# SENSOR_BOARD_2_1_layer.net
KiCad netlist of a schematic drawn in EAGLE
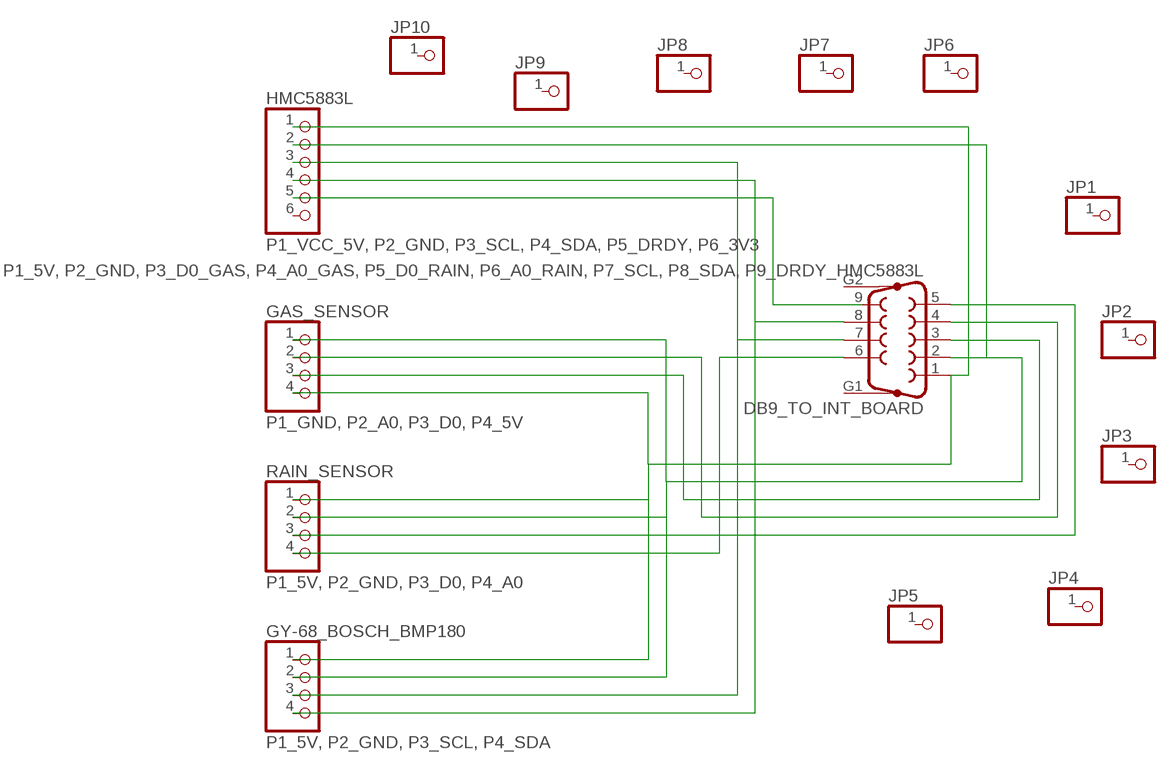
[diagram p0: schematic, sheet 1]

(export (version "E")
  (design (tool "Eeschema 10.0.6"))
  (components
    (comp (ref "DB9_TO_INT_BOARD")
      (value "P1_5V, P2_GND, P3_D0_GAS, P4_A0_GAS, P5_D0_RAIN, P6_A0_RAIN, P7_SCL, P8_SDA, P9_DRDY_HMC5883L")
      (footprint "eagle-import:F09HP")
      (libsource (lib "eagle-import") (part "F09HP"))
    )
    (comp (ref "GAS_SENSOR")
      (value "P1_GND, P2_A0, P3_D0, P4_5V")
      (footprint "eagle-import:1X04")
      (libsource (lib "eagle-import") (part "PINHD-1X4"))
    )
    (comp (ref "GY-68_BOSCH_BMP180")
      (value "P1_5V, P2_GND, P3_SCL, P4_SDA")
      (footprint "eagle-import:1X04")
      (libsource (lib "eagle-import") (part "PINHD-1X4"))
    )
    (comp (ref "HMC5883L")
      (value "P1_VCC_5V, P2_GND, P3_SCL, P4_SDA, P5_DRDY, P6_3V3")
      (footprint "eagle-import:1X06")
      (libsource (lib "eagle-import") (part "PINHD-1X6"))
    )
    (comp (ref "JP1")
      (value "PINHD-1X1")
      (footprint "eagle-import:1X01")
      (libsource (lib "eagle-import") (part "PINHD-1X1"))
    )
    (comp (ref "JP2")
      (value "PINHD-1X1")
      (footprint "eagle-import:1X01")
      (libsource (lib "eagle-import") (part "PINHD-1X1"))
    )
    (comp (ref "JP3")
      (value "PINHD-1X1")
      (footprint "eagle-import:1X01")
      (libsource (lib "eagle-import") (part "PINHD-1X1"))
    )
    (comp (ref "JP4")
      (value "PINHD-1X1")
      (footprint "eagle-import:1X01")
      (libsource (lib "eagle-import") (part "PINHD-1X1"))
    )
    (comp (ref "JP5")
      (value "PINHD-1X1")
      (footprint "eagle-import:1X01")
      (libsource (lib "eagle-import") (part "PINHD-1X1"))
    )
    (comp (ref "JP6")
      (value "PINHD-1X1")
      (footprint "eagle-import:1X01")
      (libsource (lib "eagle-import") (part "PINHD-1X1"))
    )
    (comp (ref "JP7")
      (value "PINHD-1X1")
      (footprint "eagle-import:1X01")
      (libsource (lib "eagle-import") (part "PINHD-1X1"))
    )
    (comp (ref "JP8")
      (value "PINHD-1X1")
      (footprint "eagle-import:1X01")
      (libsource (lib "eagle-import") (part "PINHD-1X1"))
    )
    (comp (ref "JP9")
      (value "PINHD-1X1")
      (footprint "eagle-import:1X01")
      (libsource (lib "eagle-import") (part "PINHD-1X1"))
    )
    (comp (ref "JP10")
      (value "PINHD-1X1")
      (footprint "eagle-import:1X01")
      (libsource (lib "eagle-import") (part "PINHD-1X1"))
    )
    (comp (ref "RAIN_SENSOR")
      (value "P1_5V, P2_GND, P3_D0, P4_A0")
      (footprint "eagle-import:1X04")
      (libsource (lib "eagle-import") (part "PINHD-1X4"))
    )
  )
  (nets
    (net (code "1") (name "Net-(DB9_TO_INT_BOARD-Pad1)") (class "Default")
      (node (ref "DB9_TO_INT_BOARD") (pin "1") (pinfunction "1_1") (pintype "passive"))
      (node (ref "GAS_SENSOR") (pin "4") (pinfunction "4_4") (pintype "passive"))
      (node (ref "GY-68_BOSCH_BMP180") (pin "1") (pinfunction "1_1") (pintype "passive"))
      (node (ref "HMC5883L") (pin "1") (pinfunction "1_1") (pintype "passive"))
      (node (ref "RAIN_SENSOR") (pin "1") (pinfunction "1_1") (pintype "passive"))
    )
    (net (code "2") (name "Net-(DB9_TO_INT_BOARD-Pad2)") (class "Default")
      (node (ref "DB9_TO_INT_BOARD") (pin "2") (pinfunction "2_2") (pintype "passive"))
      (node (ref "GAS_SENSOR") (pin "1") (pinfunction "1_1") (pintype "passive"))
      (node (ref "GY-68_BOSCH_BMP180") (pin "2") (pinfunction "2_2") (pintype "passive"))
      (node (ref "HMC5883L") (pin "2") (pinfunction "2_2") (pintype "passive"))
      (node (ref "RAIN_SENSOR") (pin "2") (pinfunction "2_2") (pintype "passive"))
    )
    (net (code "3") (name "Net-(DB9_TO_INT_BOARD-Pad3)") (class "Default")
      (node (ref "DB9_TO_INT_BOARD") (pin "3") (pinfunction "3_3") (pintype "passive"))
      (node (ref "GAS_SENSOR") (pin "3") (pinfunction "3_3") (pintype "passive"))
    )
    (net (code "4") (name "Net-(DB9_TO_INT_BOARD-Pad4)") (class "Default")
      (node (ref "DB9_TO_INT_BOARD") (pin "4") (pinfunction "4_4") (pintype "passive"))
      (node (ref "GAS_SENSOR") (pin "2") (pinfunction "2_2") (pintype "passive"))
    )
    (net (code "5") (name "Net-(DB9_TO_INT_BOARD-Pad5)") (class "Default")
      (node (ref "DB9_TO_INT_BOARD") (pin "5") (pinfunction "5_5") (pintype "passive"))
      (node (ref "RAIN_SENSOR") (pin "3") (pinfunction "3_3") (pintype "passive"))
    )
    (net (code "6") (name "Net-(DB9_TO_INT_BOARD-Pad6)") (class "Default")
      (node (ref "DB9_TO_INT_BOARD") (pin "6") (pinfunction "6_6") (pintype "passive"))
      (node (ref "RAIN_SENSOR") (pin "4") (pinfunction "4_4") (pintype "passive"))
    )
    (net (code "7") (name "Net-(DB9_TO_INT_BOARD-Pad7)") (class "Default")
      (node (ref "DB9_TO_INT_BOARD") (pin "7") (pinfunction "7_7") (pintype "passive"))
      (node (ref "GY-68_BOSCH_BMP180") (pin "3") (pinfunction "3_3") (pintype "passive"))
      (node (ref "HMC5883L") (pin "3") (pinfunction "3_3") (pintype "passive"))
    )
    (net (code "8") (name "Net-(DB9_TO_INT_BOARD-Pad8)") (class "Default")
      (node (ref "DB9_TO_INT_BOARD") (pin "8") (pinfunction "8_8") (pintype "passive"))
      (node (ref "GY-68_BOSCH_BMP180") (pin "4") (pinfunction "4_4") (pintype "passive"))
      (node (ref "HMC5883L") (pin "4") (pinfunction "4_4") (pintype "passive"))
    )
    (net (code "9") (name "unconnected-(DB9_TO_INT_BOARD-Pad9)") (class "Default")
      (node (ref "DB9_TO_INT_BOARD") (pin "9") (pinfunction "9_9") (pintype "passive"))
    )
    (net (code "10") (name "unconnected-(DB9_TO_INT_BOARD-PadG1)") (class "Default")
      (node (ref "DB9_TO_INT_BOARD") (pin "G1") (pinfunction "G1_G1") (pintype "passive"))
    )
    (net (code "11") (name "unconnected-(DB9_TO_INT_BOARD-PadG2)") (class "Default")
      (node (ref "DB9_TO_INT_BOARD") (pin "G2") (pinfunction "G2_G2") (pintype "passive"))
    )
    (net (code "12") (name "unconnected-(HMC5883L-Pad5)") (class "Default")
      (node (ref "HMC5883L") (pin "5") (pinfunction "5_5") (pintype "passive"))
    )
    (net (code "13") (name "unconnected-(HMC5883L-Pad6)") (class "Default")
      (node (ref "HMC5883L") (pin "6") (pinfunction "6_6") (pintype "passive"))
    )
    (net (code "14") (name "unconnected-(JP1-Pad1)") (class "Default")
      (node (ref "JP1") (pin "1") (pinfunction "1_1") (pintype "passive"))
    )
    (net (code "15") (name "unconnected-(JP2-Pad1)") (class "Default")
      (node (ref "JP2") (pin "1") (pinfunction "1_1") (pintype "passive"))
    )
    (net (code "16") (name "unconnected-(JP3-Pad1)") (class "Default")
      (node (ref "JP3") (pin "1") (pinfunction "1_1") (pintype "passive"))
    )
    (net (code "17") (name "unconnected-(JP4-Pad1)") (class "Default")
      (node (ref "JP4") (pin "1") (pinfunction "1_1") (pintype "passive"))
    )
    (net (code "18") (name "unconnected-(JP5-Pad1)") (class "Default")
      (node (ref "JP5") (pin "1") (pinfunction "1_1") (pintype "passive"))
    )
    (net (code "19") (name "unconnected-(JP6-Pad1)") (class "Default")
      (node (ref "JP6") (pin "1") (pinfunction "1_1") (pintype "passive"))
    )
    (net (code "20") (name "unconnected-(JP7-Pad1)") (class "Default")
      (node (ref "JP7") (pin "1") (pinfunction "1_1") (pintype "passive"))
    )
    (net (code "21") (name "unconnected-(JP8-Pad1)") (class "Default")
      (node (ref "JP8") (pin "1") (pinfunction "1_1") (pintype "passive"))
    )
    (net (code "22") (name "unconnected-(JP9-Pad1)") (class "Default")
      (node (ref "JP9") (pin "1") (pinfunction "1_1") (pintype "passive"))
    )
    (net (code "23") (name "unconnected-(JP10-Pad1)") (class "Default")
      (node (ref "JP10") (pin "1") (pinfunction "1_1") (pintype "passive"))
    )
  )
)
